# MB1296-LRA_Module.net
KiCad netlist of a schematic drawn in Altium Designer
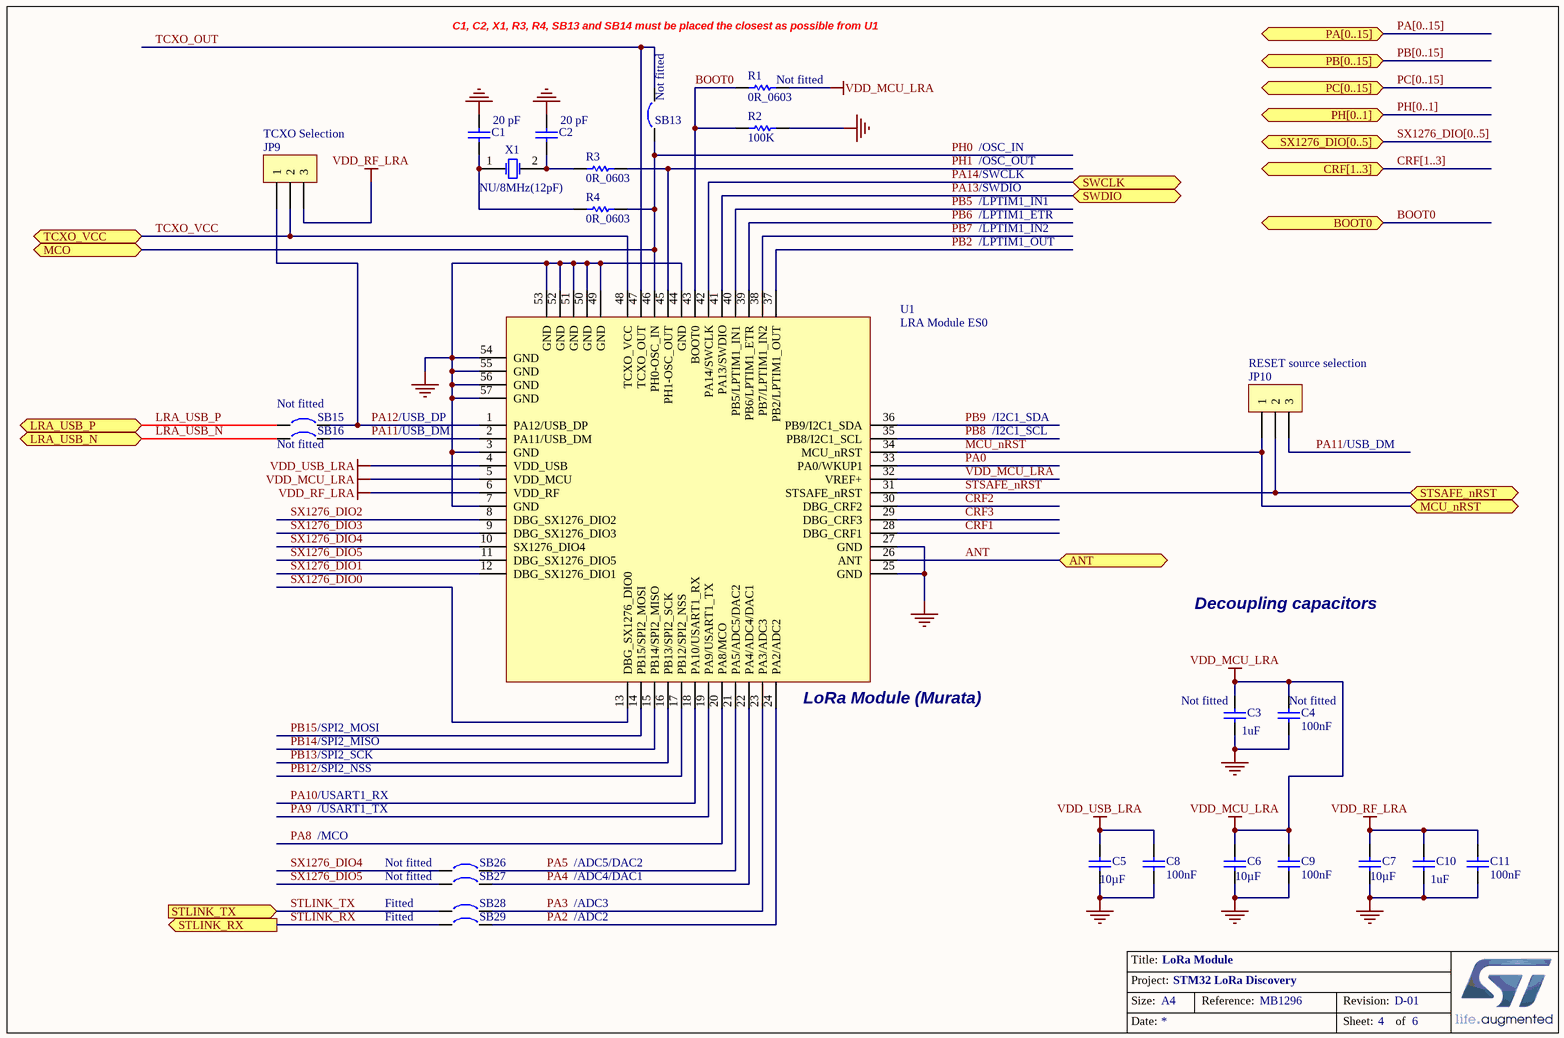
[diagram p0: MB1296-LRA_Module.SchDoc]

(export (version "E")
  (design (tool "Eeschema 10.0.6"))
  (components
    (comp (ref "C1")
      (value "20 pF")
      (footprint "0603C")
      (description "Capacitor 0603")
      (fields (field (name "MANUFACTURER") "YAGEO") (field (name "PROVIDED BY") "Subcon"))
      (libsource (lib "MCD16-033-STM32_LRA_Eval_Board_1") (part "Capacitor_ST"))
    )
    (comp (ref "C2")
      (value "20 pF")
      (footprint "0603C")
      (description "Capacitor 0603")
      (fields (field (name "MANUFACTURER") "YAGEO") (field (name "PROVIDED BY") "Subcon"))
      (libsource (lib "MCD16-033-STM32_LRA_Eval_Board_1") (part "Capacitor_ST"))
    )
    (comp (ref "C3")
      (value "1uF")
      (footprint "0603C")
      (description "0603  X5R 1µF")
      (fields (field (name "MANUFACTURER") "YAGEO") (field (name "PROVIDED BY") "Subcon"))
      (libsource (lib "MCD16-033-STM32_LRA_Eval_Board_1") (part "CAP SMD 0603  X5R 1µF 25V 10%"))
    )
    (comp (ref "C4")
      (value "100nF")
      (footprint "0603C")
      (description "Capacitor 100nF")
      (fields (field (name "MANUFACTURER") "YAGEO") (field (name "PROVIDED BY") "Subcon"))
      (libsource (lib "MCD16-033-STM32_LRA_Eval_Board_1") (part "CAP"))
    )
    (comp (ref "C5")
      (value "10µF")
      (footprint "0603C")
      (description "Capacitor SMD 0805 10000000pF X7R 10V +/-10%")
      (fields (field (name "MANUFACTURER") "Kemet") (field (name "TOLERANCE") "10%"))
      (libsource (lib "Capacitor_0805") (part "CAP_C0805C106K8RACTU"))
    )
    (comp (ref "C6")
      (value "10µF")
      (footprint "0603C")
      (description "Capacitor SMD 0805 10000000pF X7R 10V +/-10%")
      (fields (field (name "MANUFACTURER") "Kemet") (field (name "TOLERANCE") "10%"))
      (libsource (lib "Capacitor_0805") (part "CAP_C0805C106K8RACTU"))
    )
    (comp (ref "C7")
      (value "10µF")
      (footprint "0603C")
      (description "Capacitor SMD 0805 10000000pF X7R 10V +/-10%")
      (fields (field (name "MANUFACTURER") "Kemet") (field (name "TOLERANCE") "10%"))
      (libsource (lib "Capacitor_0805") (part "CAP_C0805C106K8RACTU"))
    )
    (comp (ref "C8")
      (value "100nF")
      (footprint "0603C")
      (description "Capacitor 100nF")
      (fields (field (name "MANUFACTURER") "YAGEO") (field (name "PROVIDED BY") "Subcon"))
      (libsource (lib "MCD16-033-STM32_LRA_Eval_Board_1") (part "CAP"))
    )
    (comp (ref "C9")
      (value "100nF")
      (footprint "0603C")
      (description "Capacitor 100nF")
      (fields (field (name "MANUFACTURER") "YAGEO") (field (name "PROVIDED BY") "Subcon"))
      (libsource (lib "MCD16-033-STM32_LRA_Eval_Board_1") (part "CAP"))
    )
    (comp (ref "C10")
      (value "1uF")
      (footprint "0603C")
      (description "0603  X5R 1µF")
      (fields (field (name "MANUFACTURER") "YAGEO") (field (name "PROVIDED BY") "Subcon"))
      (libsource (lib "MCD16-033-STM32_LRA_Eval_Board_1") (part "CAP SMD 0603  X5R 1µF 25V 10%"))
    )
    (comp (ref "C11")
      (value "100nF")
      (footprint "0603C")
      (description "Capacitor 100nF")
      (fields (field (name "MANUFACTURER") "YAGEO") (field (name "PROVIDED BY") "Subcon"))
      (libsource (lib "MCD16-033-STM32_LRA_Eval_Board_1") (part "CAP"))
    )
    (comp (ref "JP9")
      (value "TCXO Selection")
      (footprint "SIP3")
      (description "Header 3")
      (fields (field (name "MANUFACTURER") "Kontek") (field (name "PROVIDED BY") "Subcon"))
      (libsource (lib "MCD16-033-STM32_LRA_Eval_Board_1") (part "Header 3"))
    )
    (comp (ref "JP10")
      (value "RESET source selection")
      (footprint "SIP3")
      (description "Header 3")
      (fields (field (name "MANUFACTURER") "Kontek") (field (name "PROVIDED BY") "Subcon"))
      (libsource (lib "MCD16-033-STM32_LRA_Eval_Board_1") (part "Header 3"))
    )
    (comp (ref "R1")
      (value "0R_0603")
      (footprint "0603")
      (description "0603 0R 50V 0.1W")
      (fields (field (name "MANUFACTURER") "YAGEO"))
      (libsource (lib "Resistor_0603") (part "RES SMD 0603 0R 50V 0.1W"))
    )
    (comp (ref "R2")
      (value "100K")
      (footprint "0603")
      (description "0603 100K 75V 5% 0.1W")
      (fields (field (name "MANUFACTURER") "YAGEO") (field (name "PROVIDED BY") "Subcon"))
      (libsource (lib "MCD16-033-STM32_LRA_Eval_Board_1") (part "RES SMD 0603 100K 75V 5% 0.1W"))
    )
    (comp (ref "R3")
      (value "0R_0603")
      (footprint "0603")
      (description "0603 0R 50V 0.1W")
      (fields (field (name "MANUFACTURER") "YAGEO"))
      (libsource (lib "Resistor_0603") (part "RES SMD 0603 0R 50V 0.1W"))
    )
    (comp (ref "R4")
      (value "0R_0603")
      (footprint "0603")
      (description "0603 0R 50V 0.1W")
      (fields (field (name "MANUFACTURER") "YAGEO"))
      (libsource (lib "Resistor_0603") (part "RES SMD 0603 0R 50V 0.1W"))
    )
    (comp (ref "SB13")
      (value "Circuit Breaker")
      (footprint "JP2_SMD")
      (libsource (lib "MCD16-033-STM32_LRA_Eval_Board_1") (part "Circuit Breaker"))
    )
    (comp (ref "SB15")
      (value "Circuit Breaker")
      (footprint "JP2_SMD")
      (libsource (lib "MCD16-033-STM32_LRA_Eval_Board_1") (part "Circuit Breaker"))
    )
    (comp (ref "SB16")
      (value "Circuit Breaker")
      (footprint "JP2_SMD")
      (libsource (lib "MCD16-033-STM32_LRA_Eval_Board_1") (part "Circuit Breaker"))
    )
    (comp (ref "SB26")
      (value "Circuit Breaker")
      (footprint "JP2_SMD")
      (libsource (lib "MCD16-033-STM32_LRA_Eval_Board_1") (part "Circuit Breaker"))
    )
    (comp (ref "SB27")
      (value "Circuit Breaker")
      (footprint "JP2_SMD")
      (libsource (lib "MCD16-033-STM32_LRA_Eval_Board_1") (part "Circuit Breaker"))
    )
    (comp (ref "SB28")
      (value "Circuit Breaker")
      (footprint "JP2_SMD")
      (libsource (lib "MCD16-033-STM32_LRA_Eval_Board_1") (part "Circuit Breaker"))
    )
    (comp (ref "SB29")
      (value "Circuit Breaker")
      (footprint "JP2_SMD")
      (libsource (lib "MCD16-033-STM32_LRA_Eval_Board_1") (part "Circuit Breaker"))
    )
    (comp (ref "U1")
      (value "LRA Module ES0")
      (footprint "Lora Module ES0")
      (fields (field (name "MANUFACTURER") "Murata") (field (name "PROVIDED BY") "Murata"))
      (libsource (lib "Integrated_Circuit") (part "LRA Module ES0"))
    )
    (comp (ref "X1")
      (value "NU/8MHz(12pF)")
      (footprint "CRY_NX3225GD_2P")
      (description "Crystal Oscillator")
      (fields (field (name "MANUFACTURER") "HongKongCrystal") (field (name "PROVIDED BY") "Subcon"))
      (libsource (lib "MB963_1") (part "XTAL"))
    )
  )
  (nets
    (net (code "27") (name "/ANT") (class "Default")
      (node (ref "U1") (pin "26") (pinfunction "ANT_26") (pintype "passive"))
    )
    (net (code "28") (name "/BOOT0") (class "Default")
      (node (ref "R1") (pin "1") (pinfunction "1_1") (pintype "passive"))
      (node (ref "R2") (pin "2") (pinfunction "2_2") (pintype "passive"))
      (node (ref "U1") (pin "43") (pinfunction "BOOT0_43") (pintype "passive"))
    )
    (net (code "29") (name "/CRF1") (class "Default")
      (node (ref "U1") (pin "28") (pinfunction "DBG_CRF1_28") (pintype "passive"))
    )
    (net (code "30") (name "/CRF2") (class "Default")
      (node (ref "U1") (pin "30") (pinfunction "DBG_CRF2_30") (pintype "passive"))
    )
    (net (code "31") (name "/CRF3") (class "Default")
      (node (ref "U1") (pin "29") (pinfunction "DBG_CRF3_29") (pintype "passive"))
    )
    (net (code "33") (name "/LRA_USB_N") (class "Default")
      (node (ref "SB16") (pin "1") (pinfunction "1_1") (pintype "passive"))
    )
    (net (code "34") (name "/LRA_USB_P") (class "Default")
      (node (ref "SB15") (pin "1") (pinfunction "1_1") (pintype "passive"))
    )
    (net (code "35") (name "/MCU_nRST") (class "Default")
      (node (ref "JP10") (pin "1") (pinfunction "1_1") (pintype "passive"))
      (node (ref "U1") (pin "34") (pinfunction "MCU_nRST_34") (pintype "passive"))
    )
    (net (code "36") (name "/PA0") (class "Default")
      (node (ref "U1") (pin "33") (pinfunction "PA0/WKUP1_33") (pintype "passive"))
    )
    (net (code "37") (name "/PA2") (class "Default")
      (node (ref "SB29") (pin "2") (pinfunction "2_2") (pintype "passive"))
      (node (ref "U1") (pin "24") (pinfunction "PA2/ADC2_24") (pintype "passive"))
    )
    (net (code "38") (name "/PA3") (class "Default")
      (node (ref "SB28") (pin "2") (pinfunction "2_2") (pintype "passive"))
      (node (ref "U1") (pin "23") (pinfunction "PA3/ADC3_23") (pintype "passive"))
    )
    (net (code "39") (name "/PA4") (class "Default")
      (node (ref "SB27") (pin "2") (pinfunction "2_2") (pintype "passive"))
      (node (ref "U1") (pin "22") (pinfunction "PA4/ADC4/DAC1_22") (pintype "passive"))
    )
    (net (code "40") (name "/PA5") (class "Default")
      (node (ref "SB26") (pin "2") (pinfunction "2_2") (pintype "passive"))
      (node (ref "U1") (pin "21") (pinfunction "PA5/ADC5/DAC2_21") (pintype "passive"))
    )
    (net (code "41") (name "/PA8") (class "Default")
      (node (ref "U1") (pin "20") (pinfunction "PA8/MCO_20") (pintype "passive"))
    )
    (net (code "42") (name "/PA9") (class "Default")
      (node (ref "U1") (pin "19") (pinfunction "PA9/USART1_TX_19") (pintype "passive"))
    )
    (net (code "43") (name "/PA10") (class "Default")
      (node (ref "U1") (pin "18") (pinfunction "PA10/USART1_RX_18") (pintype "passive"))
    )
    (net (code "44") (name "/PA11") (class "Default")
      (node (ref "JP10") (pin "3") (pinfunction "3_3") (pintype "passive"))
      (node (ref "SB16") (pin "2") (pinfunction "2_2") (pintype "passive"))
      (node (ref "U1") (pin "2") (pinfunction "PA11/USB_DM_2") (pintype "passive"))
    )
    (net (code "45") (name "/PA12") (class "Default")
      (node (ref "JP9") (pin "1") (pinfunction "1_1") (pintype "passive"))
      (node (ref "SB15") (pin "2") (pinfunction "2_2") (pintype "passive"))
      (node (ref "U1") (pin "1") (pinfunction "PA12/USB_DP_1") (pintype "passive"))
    )
    (net (code "46") (name "/PA13") (class "Default")
      (node (ref "U1") (pin "41") (pinfunction "PA13/SWDIO_41") (pintype "passive"))
    )
    (net (code "47") (name "/PA14") (class "Default")
      (node (ref "U1") (pin "42") (pinfunction "PA14/SWCLK_42") (pintype "passive"))
    )
    (net (code "49") (name "/PB2") (class "Default")
      (node (ref "U1") (pin "37") (pinfunction "PB2/LPTIM1_OUT_37") (pintype "passive"))
    )
    (net (code "50") (name "/PB5") (class "Default")
      (node (ref "U1") (pin "40") (pinfunction "PB5/LPTIM1_IN1_40") (pintype "passive"))
    )
    (net (code "51") (name "/PB6") (class "Default")
      (node (ref "U1") (pin "39") (pinfunction "PB6/LPTIM1_ETR_39") (pintype "passive"))
    )
    (net (code "52") (name "/PB7") (class "Default")
      (node (ref "U1") (pin "38") (pinfunction "PB7/LPTIM1_IN2_38") (pintype "passive"))
    )
    (net (code "53") (name "/PB8") (class "Default")
      (node (ref "U1") (pin "35") (pinfunction "PB8/I2C1_SCL_35") (pintype "passive"))
    )
    (net (code "54") (name "/PB9") (class "Default")
      (node (ref "U1") (pin "36") (pinfunction "PB9/I2C1_SDA_36") (pintype "passive"))
    )
    (net (code "55") (name "/PB12") (class "Default")
      (node (ref "U1") (pin "17") (pinfunction "PB12/SPI2_NSS_17") (pintype "passive"))
    )
    (net (code "56") (name "/PB13") (class "Default")
      (node (ref "U1") (pin "16") (pinfunction "PB13/SPI2_SCK_16") (pintype "passive"))
    )
    (net (code "57") (name "/PB14") (class "Default")
      (node (ref "U1") (pin "15") (pinfunction "PB14/SPI2_MISO_15") (pintype "passive"))
    )
    (net (code "58") (name "/PB15") (class "Default")
      (node (ref "U1") (pin "14") (pinfunction "PB15/SPI2_MOSI_14") (pintype "passive"))
    )
    (net (code "61") (name "/PH0") (class "Default")
      (node (ref "R4") (pin "2") (pinfunction "2_2") (pintype "passive"))
      (node (ref "SB13") (pin "1") (pinfunction "1_1") (pintype "passive"))
      (node (ref "U1") (pin "46") (pinfunction "PH0-OSC_IN_46") (pintype "passive"))
    )
    (net (code "62") (name "/PH1") (class "Default")
      (node (ref "R3") (pin "2") (pinfunction "2_2") (pintype "passive"))
      (node (ref "U1") (pin "45") (pinfunction "PH1-OSC_OUT_45") (pintype "passive"))
    )
    (net (code "64") (name "/STLINK_RX") (class "Default")
      (node (ref "SB29") (pin "1") (pinfunction "1_1") (pintype "passive"))
    )
    (net (code "65") (name "/STLINK_TX") (class "Default")
      (node (ref "SB28") (pin "1") (pinfunction "1_1") (pintype "passive"))
    )
    (net (code "66") (name "/STSAFE_nRST") (class "Default")
      (node (ref "JP10") (pin "2") (pinfunction "2_2") (pintype "passive"))
      (node (ref "U1") (pin "31") (pinfunction "STSAFE_nRST_31") (pintype "passive"))
    )
    (net (code "67") (name "/SX1276_DIO0") (class "Default")
      (node (ref "U1") (pin "13") (pinfunction "DBG_SX1276_DIO0_13") (pintype "passive"))
    )
    (net (code "68") (name "/SX1276_DIO1") (class "Default")
      (node (ref "U1") (pin "12") (pinfunction "DBG_SX1276_DIO1_12") (pintype "passive"))
    )
    (net (code "69") (name "/SX1276_DIO2") (class "Default")
      (node (ref "U1") (pin "8") (pinfunction "DBG_SX1276_DIO2_8") (pintype "passive"))
    )
    (net (code "70") (name "/SX1276_DIO3") (class "Default")
      (node (ref "U1") (pin "9") (pinfunction "DBG_SX1276_DIO3_9") (pintype "passive"))
    )
    (net (code "71") (name "/SX1276_DIO4") (class "Default")
      (node (ref "SB26") (pin "1") (pinfunction "1_1") (pintype "passive"))
      (node (ref "U1") (pin "10") (pinfunction "SX1276_DIO4_10") (pintype "passive"))
    )
    (net (code "72") (name "/SX1276_DIO5") (class "Default")
      (node (ref "SB27") (pin "1") (pinfunction "1_1") (pintype "passive"))
      (node (ref "U1") (pin "11") (pinfunction "DBG_SX1276_DIO5_11") (pintype "passive"))
    )
    (net (code "74") (name "/TCXO_OUT") (class "Default")
      (node (ref "SB13") (pin "2") (pinfunction "2_2") (pintype "passive"))
      (node (ref "U1") (pin "47") (pinfunction "TCXO_OUT_47") (pintype "passive"))
    )
    (net (code "75") (name "/TCXO_VCC") (class "Default")
      (node (ref "JP9") (pin "2") (pinfunction "2_2") (pintype "passive"))
      (node (ref "U1") (pin "48") (pinfunction "TCXO_VCC_48") (pintype "passive"))
    )
    (net (code "76") (name "GND") (class "Default")
      (node (ref "C1") (pin "2") (pinfunction "2_2") (pintype "passive"))
      (node (ref "C10") (pin "1") (pinfunction "1_1") (pintype "passive"))
      (node (ref "C11") (pin "1") (pinfunction "1_1") (pintype "passive"))
      (node (ref "C2") (pin "2") (pinfunction "2_2") (pintype "passive"))
      (node (ref "C3") (pin "1") (pinfunction "1_1") (pintype "passive"))
      (node (ref "C4") (pin "1") (pinfunction "1_1") (pintype "passive"))
      (node (ref "C5") (pin "2") (pinfunction "2_2") (pintype "passive"))
      (node (ref "C6") (pin "2") (pinfunction "2_2") (pintype "passive"))
      (node (ref "C7") (pin "2") (pinfunction "2_2") (pintype "passive"))
      (node (ref "C8") (pin "1") (pinfunction "1_1") (pintype "passive"))
      (node (ref "C9") (pin "1") (pinfunction "1_1") (pintype "passive"))
      (node (ref "R2") (pin "1") (pinfunction "1_1") (pintype "passive"))
      (node (ref "U1") (pin "25") (pinfunction "GND_25") (pintype "passive"))
      (node (ref "U1") (pin "27") (pinfunction "GND_27") (pintype "passive"))
      (node (ref "U1") (pin "3") (pinfunction "GND_3") (pintype "passive"))
      (node (ref "U1") (pin "44") (pinfunction "GND_44") (pintype "passive"))
      (node (ref "U1") (pin "49") (pinfunction "GND_49") (pintype "passive"))
      (node (ref "U1") (pin "50") (pinfunction "GND_50") (pintype "passive"))
      (node (ref "U1") (pin "51") (pinfunction "GND_51") (pintype "passive"))
      (node (ref "U1") (pin "52") (pinfunction "GND_52") (pintype "passive"))
      (node (ref "U1") (pin "53") (pinfunction "GND_53") (pintype "passive"))
      (node (ref "U1") (pin "54") (pinfunction "GND_54") (pintype "passive"))
      (node (ref "U1") (pin "55") (pinfunction "GND_55") (pintype "passive"))
      (node (ref "U1") (pin "56") (pinfunction "GND_56") (pintype "passive"))
      (node (ref "U1") (pin "57") (pinfunction "GND_57") (pintype "passive"))
      (node (ref "U1") (pin "7") (pinfunction "GND_7") (pintype "passive"))
    )
    (net (code "77") (name "Net-(X1-OSC1)") (class "Default")
      (node (ref "C1") (pin "1") (pinfunction "1_1") (pintype "passive"))
      (node (ref "R4") (pin "1") (pinfunction "1_1") (pintype "passive"))
      (node (ref "X1") (pin "1") (pinfunction "OSC1_1") (pintype "passive"))
    )
    (net (code "78") (name "Net-(X1-OSC2)") (class "Default")
      (node (ref "C2") (pin "1") (pinfunction "1_1") (pintype "passive"))
      (node (ref "R3") (pin "1") (pinfunction "1_1") (pintype "passive"))
      (node (ref "X1") (pin "2") (pinfunction "OSC2_2") (pintype "passive"))
    )
    (net (code "79") (name "VDD_MCU_LRA") (class "Default")
      (node (ref "C3") (pin "2") (pinfunction "2_2") (pintype "passive"))
      (node (ref "C4") (pin "2") (pinfunction "2_2") (pintype "passive"))
      (node (ref "C6") (pin "1") (pinfunction "1_1") (pintype "passive"))
      (node (ref "C9") (pin "2") (pinfunction "2_2") (pintype "passive"))
      (node (ref "R1") (pin "2") (pinfunction "2_2") (pintype "passive"))
      (node (ref "U1") (pin "32") (pinfunction "VREF+_32") (pintype "passive"))
      (node (ref "U1") (pin "5") (pinfunction "VDD_MCU_5") (pintype "passive"))
    )
    (net (code "80") (name "VDD_RF_LRA") (class "Default")
      (node (ref "C10") (pin "2") (pinfunction "2_2") (pintype "passive"))
      (node (ref "C11") (pin "2") (pinfunction "2_2") (pintype "passive"))
      (node (ref "C7") (pin "1") (pinfunction "1_1") (pintype "passive"))
      (node (ref "JP9") (pin "3") (pinfunction "3_3") (pintype "passive"))
      (node (ref "U1") (pin "6") (pinfunction "VDD_RF_6") (pintype "passive"))
    )
    (net (code "81") (name "VDD_USB_LRA") (class "Default")
      (node (ref "C5") (pin "1") (pinfunction "1_1") (pintype "passive"))
      (node (ref "C8") (pin "2") (pinfunction "2_2") (pintype "passive"))
      (node (ref "U1") (pin "4") (pinfunction "VDD_USB_4") (pintype "passive"))
    )
  )
)
